# Oscilloscope.net
KiCad netlist of a schematic drawn in EAGLE
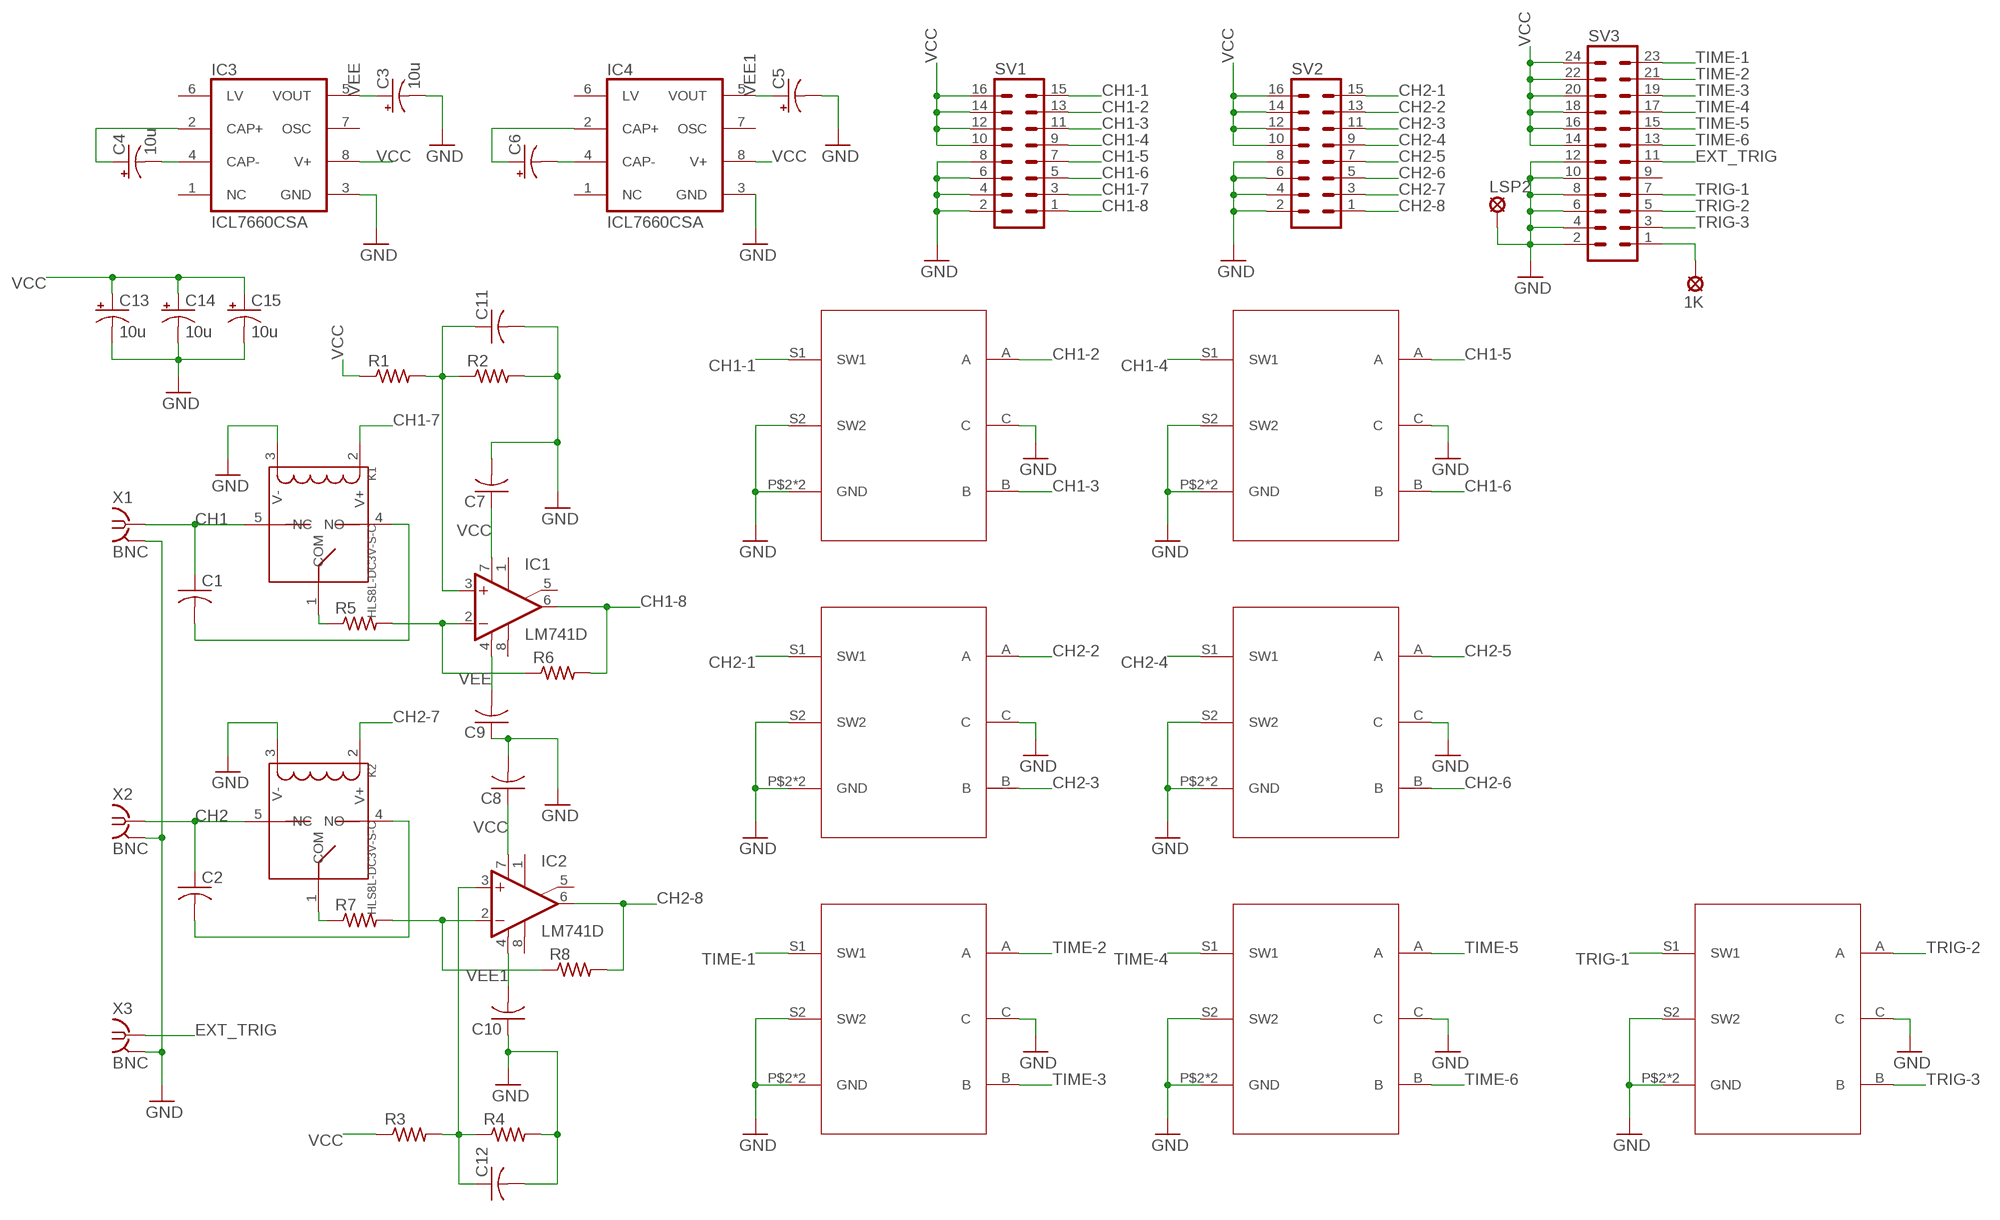
[diagram p0: schematic, sheet 1]

(export (version "E")
  (design (tool "Eeschema 10.0.6"))
  (components
    (comp (ref "1K")
      (value "LSP11")
      (footprint "eagle-import:LSP11")
      (libsource (lib "eagle-import") (part "LSP11"))
    )
    (comp (ref "C1")
      (value "C-USC0402K")
      (footprint "eagle-import:C0402K")
      (libsource (lib "eagle-import") (part "C-USC0402K"))
    )
    (comp (ref "C2")
      (value "C-USC0402")
      (footprint "eagle-import:C0402")
      (libsource (lib "eagle-import") (part "C-USC0402"))
    )
    (comp (ref "C3")
      (value "10u")
      (footprint "eagle-import:E2-5")
      (libsource (lib "eagle-import") (part "CPOL-USE2-5"))
    )
    (comp (ref "C4")
      (value "10u")
      (footprint "eagle-import:E2-5")
      (libsource (lib "eagle-import") (part "CPOL-USE2-5"))
    )
    (comp (ref "C5")
      (value "CPOL-USE2-5")
      (footprint "eagle-import:E2-5")
      (libsource (lib "eagle-import") (part "CPOL-USE2-5"))
    )
    (comp (ref "C6")
      (value "CPOL-USE2-5")
      (footprint "eagle-import:E2-5")
      (libsource (lib "eagle-import") (part "CPOL-USE2-5"))
    )
    (comp (ref "C7")
      (value "C-USC0402")
      (footprint "eagle-import:C0402")
      (libsource (lib "eagle-import") (part "C-USC0402"))
    )
    (comp (ref "C8")
      (value "C-USC0402")
      (footprint "eagle-import:C0402")
      (libsource (lib "eagle-import") (part "C-USC0402"))
    )
    (comp (ref "C9")
      (value "C-USC0402")
      (footprint "eagle-import:C0402")
      (libsource (lib "eagle-import") (part "C-USC0402"))
    )
    (comp (ref "C10")
      (value "C-USC0402")
      (footprint "eagle-import:C0402")
      (libsource (lib "eagle-import") (part "C-USC0402"))
    )
    (comp (ref "C11")
      (value "C-USC0402")
      (footprint "eagle-import:C0402")
      (libsource (lib "eagle-import") (part "C-USC0402"))
    )
    (comp (ref "C12")
      (value "C-USC0402K")
      (footprint "eagle-import:C0402K")
      (libsource (lib "eagle-import") (part "C-USC0402K"))
    )
    (comp (ref "C13")
      (value "10u")
      (footprint "eagle-import:E2-5")
      (libsource (lib "eagle-import") (part "CPOL-USE2-5"))
    )
    (comp (ref "C14")
      (value "10u")
      (footprint "eagle-import:E2-5")
      (libsource (lib "eagle-import") (part "CPOL-USE2-5"))
    )
    (comp (ref "C15")
      (value "10u")
      (footprint "eagle-import:E2-5")
      (libsource (lib "eagle-import") (part "CPOL-USE2-5"))
    )
    (comp (ref "IC1")
      (value "LM741D")
      (footprint "eagle-import:SO08")
      (libsource (lib "eagle-import") (part "741DLM"))
    )
    (comp (ref "IC2")
      (value "LM741D")
      (footprint "eagle-import:SO08")
      (libsource (lib "eagle-import") (part "741DLM"))
    )
    (comp (ref "IC3")
      (value "ICL7660CSA")
      (footprint "eagle-import:SO08")
      (fields (field (name "MF") "MAXIM"))
      (libsource (lib "eagle-import") (part "ICL7660CSA"))
    )
    (comp (ref "IC4")
      (value "ICL7660CSA")
      (footprint "eagle-import:SO08")
      (fields (field (name "MF") "MAXIM"))
      (libsource (lib "eagle-import") (part "ICL7660CSA"))
    )
    (comp (ref "K1")
      (value "HLS8L-DC3V-S-C")
      (footprint "eagle-import:REY5-19.0X15.0X15.0MM")
      (libsource (lib "eagle-import") (part "RELAY-HLS8L-DC3V-S-C(5P-19X15MM)"))
    )
    (comp (ref "K2")
      (value "HLS8L-DC3V-S-C")
      (footprint "eagle-import:REY5-19.0X15.0X15.0MM")
      (libsource (lib "eagle-import") (part "RELAY-HLS8L-DC3V-S-C(5P-19X15MM)"))
    )
    (comp (ref "LSP2")
      (value "LSP11")
      (footprint "eagle-import:LSP11")
      (libsource (lib "eagle-import") (part "LSP11"))
    )
    (comp (ref "R1")
      (value "R-US_R0402")
      (footprint "eagle-import:R0402")
      (libsource (lib "eagle-import") (part "R-US_R0402"))
    )
    (comp (ref "R2")
      (value "R-US_R0402")
      (footprint "eagle-import:R0402")
      (libsource (lib "eagle-import") (part "R-US_R0402"))
    )
    (comp (ref "R3")
      (value "R-US_R0402")
      (footprint "eagle-import:R0402")
      (libsource (lib "eagle-import") (part "R-US_R0402"))
    )
    (comp (ref "R4")
      (value "R-US_R0402")
      (footprint "eagle-import:R0402")
      (libsource (lib "eagle-import") (part "R-US_R0402"))
    )
    (comp (ref "R5")
      (value "R-US_R0402")
      (footprint "eagle-import:R0402")
      (libsource (lib "eagle-import") (part "R-US_R0402"))
    )
    (comp (ref "R6")
      (value "R-US_R0402")
      (footprint "eagle-import:R0402")
      (libsource (lib "eagle-import") (part "R-US_R0402"))
    )
    (comp (ref "R7")
      (value "R-US_R0402")
      (footprint "eagle-import:R0402")
      (libsource (lib "eagle-import") (part "R-US_R0402"))
    )
    (comp (ref "R8")
      (value "R-US_R0402")
      (footprint "eagle-import:R0402")
      (libsource (lib "eagle-import") (part "R-US_R0402"))
    )
    (comp (ref "SV1")
      (value "MA08-2")
      (footprint "eagle-import:MA08-2")
      (libsource (lib "eagle-import") (part "MA08-2"))
    )
    (comp (ref "SV2")
      (value "MA08-2")
      (footprint "eagle-import:MA08-2")
      (libsource (lib "eagle-import") (part "MA08-2"))
    )
    (comp (ref "SV3")
      (value "MA12-2")
      (footprint "eagle-import:MA12-2")
      (libsource (lib "eagle-import") (part "MA12-2"))
    )
    (comp (ref "U$2")
      (value "EC11S")
      (footprint "eagle-import:EC11S")
      (libsource (lib "eagle-import") (part "EC11S"))
    )
    (comp (ref "U$3")
      (value "EC11S")
      (footprint "eagle-import:EC11S")
      (libsource (lib "eagle-import") (part "EC11S"))
    )
    (comp (ref "U$4")
      (value "EC11S")
      (footprint "eagle-import:EC11S")
      (libsource (lib "eagle-import") (part "EC11S"))
    )
    (comp (ref "U$5")
      (value "EC11S")
      (footprint "eagle-import:EC11S")
      (libsource (lib "eagle-import") (part "EC11S"))
    )
    (comp (ref "U$6")
      (value "EC11S")
      (footprint "eagle-import:EC11S")
      (libsource (lib "eagle-import") (part "EC11S"))
    )
    (comp (ref "U$7")
      (value "EC11S")
      (footprint "eagle-import:EC11S")
      (libsource (lib "eagle-import") (part "EC11S"))
    )
    (comp (ref "U$8")
      (value "EC11S")
      (footprint "eagle-import:EC11S")
      (libsource (lib "eagle-import") (part "EC11S"))
    )
    (comp (ref "X1")
      (value "BNC")
      (footprint "eagle-import:BNC")
      (libsource (lib "eagle-import") (part "BNC"))
    )
    (comp (ref "X2")
      (value "BNC")
      (footprint "eagle-import:BNC")
      (libsource (lib "eagle-import") (part "BNC"))
    )
    (comp (ref "X3")
      (value "BNC")
      (footprint "eagle-import:BNC")
      (libsource (lib "eagle-import") (part "BNC"))
    )
  )
  (nets
    (net (code "1") (name "/CH1") (class "Default")
      (node (ref "C1") (pin "1") (pinfunction "1_1") (pintype "passive"))
      (node (ref "K1") (pin "5") (pinfunction "NC_5") (pintype "bidirectional"))
      (node (ref "X1") (pin "P$1") (pinfunction "SIG_P$1") (pintype "passive"))
    )
    (net (code "2") (name "/CH1-1") (class "Default")
      (node (ref "SV1") (pin "15") (pinfunction "15_15") (pintype "passive"))
      (node (ref "U$3") (pin "S1") (pinfunction "SW1_S1") (pintype "bidirectional"))
    )
    (net (code "3") (name "/CH1-2") (class "Default")
      (node (ref "SV1") (pin "13") (pinfunction "13_13") (pintype "passive"))
      (node (ref "U$3") (pin "A") (pinfunction "A_A") (pintype "bidirectional"))
    )
    (net (code "4") (name "/CH1-3") (class "Default")
      (node (ref "SV1") (pin "11") (pinfunction "11_11") (pintype "passive"))
      (node (ref "U$3") (pin "B") (pinfunction "B_B") (pintype "bidirectional"))
    )
    (net (code "5") (name "/CH1-4") (class "Default")
      (node (ref "SV1") (pin "9") (pinfunction "9_9") (pintype "passive"))
      (node (ref "U$4") (pin "S1") (pinfunction "SW1_S1") (pintype "bidirectional"))
    )
    (net (code "6") (name "/CH1-5") (class "Default")
      (node (ref "SV1") (pin "7") (pinfunction "7_7") (pintype "passive"))
      (node (ref "U$4") (pin "A") (pinfunction "A_A") (pintype "bidirectional"))
    )
    (net (code "7") (name "/CH1-6") (class "Default")
      (node (ref "SV1") (pin "5") (pinfunction "5_5") (pintype "passive"))
      (node (ref "U$4") (pin "B") (pinfunction "B_B") (pintype "bidirectional"))
    )
    (net (code "8") (name "/CH1-7") (class "Default")
      (node (ref "K1") (pin "2") (pinfunction "V+_2") (pintype "bidirectional"))
      (node (ref "SV1") (pin "3") (pinfunction "3_3") (pintype "passive"))
    )
    (net (code "9") (name "/CH1-8") (class "Default")
      (node (ref "IC1") (pin "6") (pinfunction "OUT_6") (pintype "output"))
      (node (ref "R6") (pin "2") (pinfunction "2_2") (pintype "passive"))
      (node (ref "SV1") (pin "1") (pinfunction "1_1") (pintype "passive"))
    )
    (net (code "10") (name "/CH2") (class "Default")
      (node (ref "C2") (pin "1") (pinfunction "1_1") (pintype "passive"))
      (node (ref "K2") (pin "5") (pinfunction "NC_5") (pintype "bidirectional"))
      (node (ref "X2") (pin "P$1") (pinfunction "SIG_P$1") (pintype "passive"))
    )
    (net (code "11") (name "/CH2-1") (class "Default")
      (node (ref "SV2") (pin "15") (pinfunction "15_15") (pintype "passive"))
      (node (ref "U$2") (pin "S1") (pinfunction "SW1_S1") (pintype "bidirectional"))
    )
    (net (code "12") (name "/CH2-2") (class "Default")
      (node (ref "SV2") (pin "13") (pinfunction "13_13") (pintype "passive"))
      (node (ref "U$2") (pin "A") (pinfunction "A_A") (pintype "bidirectional"))
    )
    (net (code "13") (name "/CH2-3") (class "Default")
      (node (ref "SV2") (pin "11") (pinfunction "11_11") (pintype "passive"))
      (node (ref "U$2") (pin "B") (pinfunction "B_B") (pintype "bidirectional"))
    )
    (net (code "14") (name "/CH2-4") (class "Default")
      (node (ref "SV2") (pin "9") (pinfunction "9_9") (pintype "passive"))
      (node (ref "U$5") (pin "S1") (pinfunction "SW1_S1") (pintype "bidirectional"))
    )
    (net (code "15") (name "/CH2-5") (class "Default")
      (node (ref "SV2") (pin "7") (pinfunction "7_7") (pintype "passive"))
      (node (ref "U$5") (pin "A") (pinfunction "A_A") (pintype "bidirectional"))
    )
    (net (code "16") (name "/CH2-6") (class "Default")
      (node (ref "SV2") (pin "5") (pinfunction "5_5") (pintype "passive"))
      (node (ref "U$5") (pin "B") (pinfunction "B_B") (pintype "bidirectional"))
    )
    (net (code "17") (name "/CH2-7") (class "Default")
      (node (ref "K2") (pin "2") (pinfunction "V+_2") (pintype "bidirectional"))
      (node (ref "SV2") (pin "3") (pinfunction "3_3") (pintype "passive"))
    )
    (net (code "18") (name "/CH2-8") (class "Default")
      (node (ref "IC2") (pin "6") (pinfunction "OUT_6") (pintype "output"))
      (node (ref "R8") (pin "2") (pinfunction "2_2") (pintype "passive"))
      (node (ref "SV2") (pin "1") (pinfunction "1_1") (pintype "passive"))
    )
    (net (code "19") (name "/EXT_TRIG") (class "Default")
      (node (ref "SV3") (pin "11") (pinfunction "11_11") (pintype "passive"))
      (node (ref "X3") (pin "P$1") (pinfunction "SIG_P$1") (pintype "passive"))
    )
    (net (code "20") (name "/TIME-1") (class "Default")
      (node (ref "SV3") (pin "23") (pinfunction "23_23") (pintype "passive"))
      (node (ref "U$6") (pin "S1") (pinfunction "SW1_S1") (pintype "bidirectional"))
    )
    (net (code "21") (name "/TIME-2") (class "Default")
      (node (ref "SV3") (pin "21") (pinfunction "21_21") (pintype "passive"))
      (node (ref "U$6") (pin "A") (pinfunction "A_A") (pintype "bidirectional"))
    )
    (net (code "22") (name "/TIME-3") (class "Default")
      (node (ref "SV3") (pin "19") (pinfunction "19_19") (pintype "passive"))
      (node (ref "U$6") (pin "B") (pinfunction "B_B") (pintype "bidirectional"))
    )
    (net (code "23") (name "/TIME-4") (class "Default")
      (node (ref "SV3") (pin "17") (pinfunction "17_17") (pintype "passive"))
      (node (ref "U$7") (pin "S1") (pinfunction "SW1_S1") (pintype "bidirectional"))
    )
    (net (code "24") (name "/TIME-5") (class "Default")
      (node (ref "SV3") (pin "15") (pinfunction "15_15") (pintype "passive"))
      (node (ref "U$7") (pin "A") (pinfunction "A_A") (pintype "bidirectional"))
    )
    (net (code "25") (name "/TIME-6") (class "Default")
      (node (ref "SV3") (pin "13") (pinfunction "13_13") (pintype "passive"))
      (node (ref "U$7") (pin "B") (pinfunction "B_B") (pintype "bidirectional"))
    )
    (net (code "26") (name "/TRIG-1") (class "Default")
      (node (ref "SV3") (pin "7") (pinfunction "7_7") (pintype "passive"))
      (node (ref "U$8") (pin "S1") (pinfunction "SW1_S1") (pintype "bidirectional"))
    )
    (net (code "27") (name "/TRIG-2") (class "Default")
      (node (ref "SV3") (pin "5") (pinfunction "5_5") (pintype "passive"))
      (node (ref "U$8") (pin "A") (pinfunction "A_A") (pintype "bidirectional"))
    )
    (net (code "28") (name "/TRIG-3") (class "Default")
      (node (ref "SV3") (pin "3") (pinfunction "3_3") (pintype "passive"))
      (node (ref "U$8") (pin "B") (pinfunction "B_B") (pintype "bidirectional"))
    )
    (net (code "29") (name "/VCC") (class "Default")
      (node (ref "C13") (pin "+") (pinfunction "+_+") (pintype "passive"))
      (node (ref "C14") (pin "+") (pinfunction "+_+") (pintype "passive"))
      (node (ref "C15") (pin "+") (pinfunction "+_+") (pintype "passive"))
      (node (ref "C7") (pin "1") (pinfunction "1_1") (pintype "passive"))
      (node (ref "C8") (pin "1") (pinfunction "1_1") (pintype "passive"))
      (node (ref "IC1") (pin "7") (pinfunction "V+_7") (pintype "power_in"))
      (node (ref "IC2") (pin "7") (pinfunction "V+_7") (pintype "power_in"))
      (node (ref "IC3") (pin "8") (pinfunction "V+_8") (pintype "power_in"))
      (node (ref "IC4") (pin "8") (pinfunction "V+_8") (pintype "power_in"))
      (node (ref "R1") (pin "1") (pinfunction "1_1") (pintype "passive"))
      (node (ref "R3") (pin "1") (pinfunction "1_1") (pintype "passive"))
      (node (ref "SV1") (pin "10") (pinfunction "10_10") (pintype "passive"))
      (node (ref "SV1") (pin "12") (pinfunction "12_12") (pintype "passive"))
      (node (ref "SV1") (pin "14") (pinfunction "14_14") (pintype "passive"))
      (node (ref "SV1") (pin "16") (pinfunction "16_16") (pintype "passive"))
      (node (ref "SV2") (pin "10") (pinfunction "10_10") (pintype "passive"))
      (node (ref "SV2") (pin "12") (pinfunction "12_12") (pintype "passive"))
      (node (ref "SV2") (pin "14") (pinfunction "14_14") (pintype "passive"))
      (node (ref "SV2") (pin "16") (pinfunction "16_16") (pintype "passive"))
      (node (ref "SV3") (pin "14") (pinfunction "14_14") (pintype "passive"))
      (node (ref "SV3") (pin "16") (pinfunction "16_16") (pintype "passive"))
      (node (ref "SV3") (pin "18") (pinfunction "18_18") (pintype "passive"))
      (node (ref "SV3") (pin "20") (pinfunction "20_20") (pintype "passive"))
      (node (ref "SV3") (pin "22") (pinfunction "22_22") (pintype "passive"))
      (node (ref "SV3") (pin "24") (pinfunction "24_24") (pintype "passive"))
    )
    (net (code "30") (name "/VEE") (class "Default")
      (node (ref "C3") (pin "+") (pinfunction "+_+") (pintype "passive"))
      (node (ref "C9") (pin "2") (pinfunction "2_2") (pintype "passive"))
      (node (ref "IC1") (pin "4") (pinfunction "V-_4") (pintype "power_in"))
      (node (ref "IC3") (pin "5") (pinfunction "VOUT_5") (pintype "output"))
    )
    (net (code "31") (name "/VEE1") (class "Default")
      (node (ref "C10") (pin "2") (pinfunction "2_2") (pintype "passive"))
      (node (ref "C5") (pin "+") (pinfunction "+_+") (pintype "passive"))
      (node (ref "IC2") (pin "4") (pinfunction "V-_4") (pintype "power_in"))
      (node (ref "IC4") (pin "5") (pinfunction "VOUT_5") (pintype "output"))
    )
    (net (code "32") (name "GND") (class "Default")
      (node (ref "C10") (pin "1") (pinfunction "1_1") (pintype "passive"))
      (node (ref "C11") (pin "2") (pinfunction "2_2") (pintype "passive"))
      (node (ref "C12") (pin "2") (pinfunction "2_2") (pintype "passive"))
      (node (ref "C13") (pin "-") (pinfunction "-_-") (pintype "passive"))
      (node (ref "C14") (pin "-") (pinfunction "-_-") (pintype "passive"))
      (node (ref "C15") (pin "-") (pinfunction "-_-") (pintype "passive"))
      (node (ref "C3") (pin "-") (pinfunction "-_-") (pintype "passive"))
      (node (ref "C5") (pin "-") (pinfunction "-_-") (pintype "passive"))
      (node (ref "C7") (pin "2") (pinfunction "2_2") (pintype "passive"))
      (node (ref "C8") (pin "2") (pinfunction "2_2") (pintype "passive"))
      (node (ref "C9") (pin "1") (pinfunction "1_1") (pintype "passive"))
      (node (ref "IC3") (pin "3") (pinfunction "GND_3") (pintype "power_in"))
      (node (ref "IC4") (pin "3") (pinfunction "GND_3") (pintype "power_in"))
      (node (ref "K1") (pin "3") (pinfunction "V-_3") (pintype "bidirectional"))
      (node (ref "K2") (pin "3") (pinfunction "V-_3") (pintype "bidirectional"))
      (node (ref "LSP2") (pin "MP") (pinfunction "MP_MP") (pintype "passive"))
      (node (ref "R2") (pin "2") (pinfunction "2_2") (pintype "passive"))
      (node (ref "R4") (pin "2") (pinfunction "2_2") (pintype "passive"))
      (node (ref "SV1") (pin "2") (pinfunction "2_2") (pintype "passive"))
      (node (ref "SV1") (pin "4") (pinfunction "4_4") (pintype "passive"))
      (node (ref "SV1") (pin "6") (pinfunction "6_6") (pintype "passive"))
      (node (ref "SV1") (pin "8") (pinfunction "8_8") (pintype "passive"))
      (node (ref "SV2") (pin "2") (pinfunction "2_2") (pintype "passive"))
      (node (ref "SV2") (pin "4") (pinfunction "4_4") (pintype "passive"))
      (node (ref "SV2") (pin "6") (pinfunction "6_6") (pintype "passive"))
      (node (ref "SV2") (pin "8") (pinfunction "8_8") (pintype "passive"))
      (node (ref "SV3") (pin "10") (pinfunction "10_10") (pintype "passive"))
      (node (ref "SV3") (pin "12") (pinfunction "12_12") (pintype "passive"))
      (node (ref "SV3") (pin "2") (pinfunction "2_2") (pintype "passive"))
      (node (ref "SV3") (pin "4") (pinfunction "4_4") (pintype "passive"))
      (node (ref "SV3") (pin "6") (pinfunction "6_6") (pintype "passive"))
      (node (ref "SV3") (pin "8") (pinfunction "8_8") (pintype "passive"))
      (node (ref "U$2") (pin "C") (pinfunction "C_C") (pintype "bidirectional"))
      (node (ref "U$2") (pin "P$2") (pinfunction "GND_P$2") (pintype "bidirectional"))
      (node (ref "U$2") (pin "P$3") (pinfunction "GND_P$3") (pintype "bidirectional"))
      (node (ref "U$2") (pin "S2") (pinfunction "SW2_S2") (pintype "bidirectional"))
      (node (ref "U$3") (pin "C") (pinfunction "C_C") (pintype "bidirectional"))
      (node (ref "U$3") (pin "P$2") (pinfunction "GND_P$2") (pintype "bidirectional"))
      (node (ref "U$3") (pin "P$3") (pinfunction "GND_P$3") (pintype "bidirectional"))
      (node (ref "U$3") (pin "S2") (pinfunction "SW2_S2") (pintype "bidirectional"))
      (node (ref "U$4") (pin "C") (pinfunction "C_C") (pintype "bidirectional"))
      (node (ref "U$4") (pin "P$2") (pinfunction "GND_P$2") (pintype "bidirectional"))
      (node (ref "U$4") (pin "P$3") (pinfunction "GND_P$3") (pintype "bidirectional"))
      (node (ref "U$4") (pin "S2") (pinfunction "SW2_S2") (pintype "bidirectional"))
      (node (ref "U$5") (pin "C") (pinfunction "C_C") (pintype "bidirectional"))
      (node (ref "U$5") (pin "P$2") (pinfunction "GND_P$2") (pintype "bidirectional"))
      (node (ref "U$5") (pin "P$3") (pinfunction "GND_P$3") (pintype "bidirectional"))
      (node (ref "U$5") (pin "S2") (pinfunction "SW2_S2") (pintype "bidirectional"))
      (node (ref "U$6") (pin "C") (pinfunction "C_C") (pintype "bidirectional"))
      (node (ref "U$6") (pin "P$2") (pinfunction "GND_P$2") (pintype "bidirectional"))
      (node (ref "U$6") (pin "P$3") (pinfunction "GND_P$3") (pintype "bidirectional"))
      (node (ref "U$6") (pin "S2") (pinfunction "SW2_S2") (pintype "bidirectional"))
      (node (ref "U$7") (pin "C") (pinfunction "C_C") (pintype "bidirectional"))
      (node (ref "U$7") (pin "P$2") (pinfunction "GND_P$2") (pintype "bidirectional"))
      (node (ref "U$7") (pin "P$3") (pinfunction "GND_P$3") (pintype "bidirectional"))
      (node (ref "U$7") (pin "S2") (pinfunction "SW2_S2") (pintype "bidirectional"))
      (node (ref "U$8") (pin "C") (pinfunction "C_C") (pintype "bidirectional"))
      (node (ref "U$8") (pin "P$2") (pinfunction "GND_P$2") (pintype "bidirectional"))
      (node (ref "U$8") (pin "P$3") (pinfunction "GND_P$3") (pintype "bidirectional"))
      (node (ref "U$8") (pin "S2") (pinfunction "SW2_S2") (pintype "bidirectional"))
      (node (ref "X1") (pin "P$2") (pinfunction "GND_P$2") (pintype "passive"))
      (node (ref "X1") (pin "P$3") (pinfunction "GND_P$3") (pintype "passive"))
      (node (ref "X1") (pin "P$4") (pinfunction "GND_P$4") (pintype "passive"))
      (node (ref "X1") (pin "P$5") (pinfunction "GND_P$5") (pintype "passive"))
      (node (ref "X2") (pin "P$2") (pinfunction "GND_P$2") (pintype "passive"))
      (node (ref "X2") (pin "P$3") (pinfunction "GND_P$3") (pintype "passive"))
      (node (ref "X2") (pin "P$4") (pinfunction "GND_P$4") (pintype "passive"))
      (node (ref "X2") (pin "P$5") (pinfunction "GND_P$5") (pintype "passive"))
      (node (ref "X3") (pin "P$2") (pinfunction "GND_P$2") (pintype "passive"))
      (node (ref "X3") (pin "P$3") (pinfunction "GND_P$3") (pintype "passive"))
      (node (ref "X3") (pin "P$4") (pinfunction "GND_P$4") (pintype "passive"))
      (node (ref "X3") (pin "P$5") (pinfunction "GND_P$5") (pintype "passive"))
    )
    (net (code "33") (name "Net-(1K-PadMP)") (class "Default")
      (node (ref "1K") (pin "MP") (pinfunction "MP_MP") (pintype "passive"))
      (node (ref "SV3") (pin "1") (pinfunction "1_1") (pintype "passive"))
    )
    (net (code "34") (name "Net-(IC1-+IN)") (class "Default")
      (node (ref "C11") (pin "1") (pinfunction "1_1") (pintype "passive"))
      (node (ref "IC1") (pin "3") (pinfunction "+IN_3") (pintype "input"))
      (node (ref "R1") (pin "2") (pinfunction "2_2") (pintype "passive"))
      (node (ref "R2") (pin "1") (pinfunction "1_1") (pintype "passive"))
    )
    (net (code "35") (name "Net-(IC1--IN)") (class "Default")
      (node (ref "IC1") (pin "2") (pinfunction "-IN_2") (pintype "input"))
      (node (ref "R5") (pin "2") (pinfunction "2_2") (pintype "passive"))
      (node (ref "R6") (pin "1") (pinfunction "1_1") (pintype "passive"))
    )
    (net (code "36") (name "Net-(IC2-+IN)") (class "Default")
      (node (ref "C12") (pin "1") (pinfunction "1_1") (pintype "passive"))
      (node (ref "IC2") (pin "3") (pinfunction "+IN_3") (pintype "input"))
      (node (ref "R3") (pin "2") (pinfunction "2_2") (pintype "passive"))
      (node (ref "R4") (pin "1") (pinfunction "1_1") (pintype "passive"))
    )
    (net (code "37") (name "Net-(IC2--IN)") (class "Default")
      (node (ref "IC2") (pin "2") (pinfunction "-IN_2") (pintype "input"))
      (node (ref "R7") (pin "2") (pinfunction "2_2") (pintype "passive"))
      (node (ref "R8") (pin "1") (pinfunction "1_1") (pintype "passive"))
    )
    (net (code "38") (name "Net-(IC3-CAP+)") (class "Default")
      (node (ref "C4") (pin "+") (pinfunction "+_+") (pintype "passive"))
      (node (ref "IC3") (pin "2") (pinfunction "CAP+_2") (pintype "passive"))
    )
    (net (code "39") (name "Net-(IC3-CAP-)") (class "Default")
      (node (ref "C4") (pin "-") (pinfunction "-_-") (pintype "passive"))
      (node (ref "IC3") (pin "4") (pinfunction "CAP-_4") (pintype "passive"))
    )
    (net (code "40") (name "Net-(IC4-CAP+)") (class "Default")
      (node (ref "C6") (pin "+") (pinfunction "+_+") (pintype "passive"))
      (node (ref "IC4") (pin "2") (pinfunction "CAP+_2") (pintype "passive"))
    )
    (net (code "41") (name "Net-(IC4-CAP-)") (class "Default")
      (node (ref "C6") (pin "-") (pinfunction "-_-") (pintype "passive"))
      (node (ref "IC4") (pin "4") (pinfunction "CAP-_4") (pintype "passive"))
    )
    (net (code "42") (name "Net-(K1-COM)") (class "Default")
      (node (ref "K1") (pin "1") (pinfunction "COM_1") (pintype "bidirectional"))
      (node (ref "R5") (pin "1") (pinfunction "1_1") (pintype "passive"))
    )
    (net (code "43") (name "Net-(K1-NO)") (class "Default")
      (node (ref "C1") (pin "2") (pinfunction "2_2") (pintype "passive"))
      (node (ref "K1") (pin "4") (pinfunction "NO_4") (pintype "bidirectional"))
    )
    (net (code "44") (name "Net-(K2-COM)") (class "Default")
      (node (ref "K2") (pin "1") (pinfunction "COM_1") (pintype "bidirectional"))
      (node (ref "R7") (pin "1") (pinfunction "1_1") (pintype "passive"))
    )
    (net (code "45") (name "Net-(K2-NO)") (class "Default")
      (node (ref "C2") (pin "2") (pinfunction "2_2") (pintype "passive"))
      (node (ref "K2") (pin "4") (pinfunction "NO_4") (pintype "bidirectional"))
    )
    (net (code "46") (name "unconnected-(IC1-ON1-Pad1)") (class "Default")
      (node (ref "IC1") (pin "1") (pinfunction "ON1_1") (pintype "passive"))
    )
    (net (code "47") (name "unconnected-(IC1-ON2-Pad5)") (class "Default")
      (node (ref "IC1") (pin "5") (pinfunction "ON2_5") (pintype "passive"))
    )
    (net (code "48") (name "unconnected-(IC1-OPT-Pad8)") (class "Default")
      (node (ref "IC1") (pin "8") (pinfunction "OPT_8") (pintype "passive"))
    )
    (net (code "49") (name "unconnected-(IC2-ON1-Pad1)") (class "Default")
      (node (ref "IC2") (pin "1") (pinfunction "ON1_1") (pintype "passive"))
    )
    (net (code "50") (name "unconnected-(IC2-ON2-Pad5)") (class "Default")
      (node (ref "IC2") (pin "5") (pinfunction "ON2_5") (pintype "passive"))
    )
    (net (code "51") (name "unconnected-(IC2-OPT-Pad8)") (class "Default")
      (node (ref "IC2") (pin "8") (pinfunction "OPT_8") (pintype "passive"))
    )
    (net (code "52") (name "unconnected-(IC3-LV-Pad6)") (class "Default")
      (node (ref "IC3") (pin "6") (pinfunction "LV_6") (pintype "passive"))
    )
    (net (code "53") (name "unconnected-(IC3-NC-Pad1)") (class "Default")
      (node (ref "IC3") (pin "1") (pinfunction "NC_1") (pintype "no_connect"))
    )
    (net (code "54") (name "unconnected-(IC3-OSC-Pad7)") (class "Default")
      (node (ref "IC3") (pin "7") (pinfunction "OSC_7") (pintype "output"))
    )
    (net (code "55") (name "unconnected-(IC4-LV-Pad6)") (class "Default")
      (node (ref "IC4") (pin "6") (pinfunction "LV_6") (pintype "passive"))
    )
    (net (code "56") (name "unconnected-(IC4-NC-Pad1)") (class "Default")
      (node (ref "IC4") (pin "1") (pinfunction "NC_1") (pintype "no_connect"))
    )
    (net (code "57") (name "unconnected-(IC4-OSC-Pad7)") (class "Default")
      (node (ref "IC4") (pin "7") (pinfunction "OSC_7") (pintype "output"))
    )
    (net (code "58") (name "unconnected-(SV3-Pad9)") (class "Default")
      (node (ref "SV3") (pin "9") (pinfunction "9_9") (pintype "passive"))
    )
  )
)
